# smartGarden_Sen_Rev01.net
KiCad netlist of a schematic drawn in Altium Designer
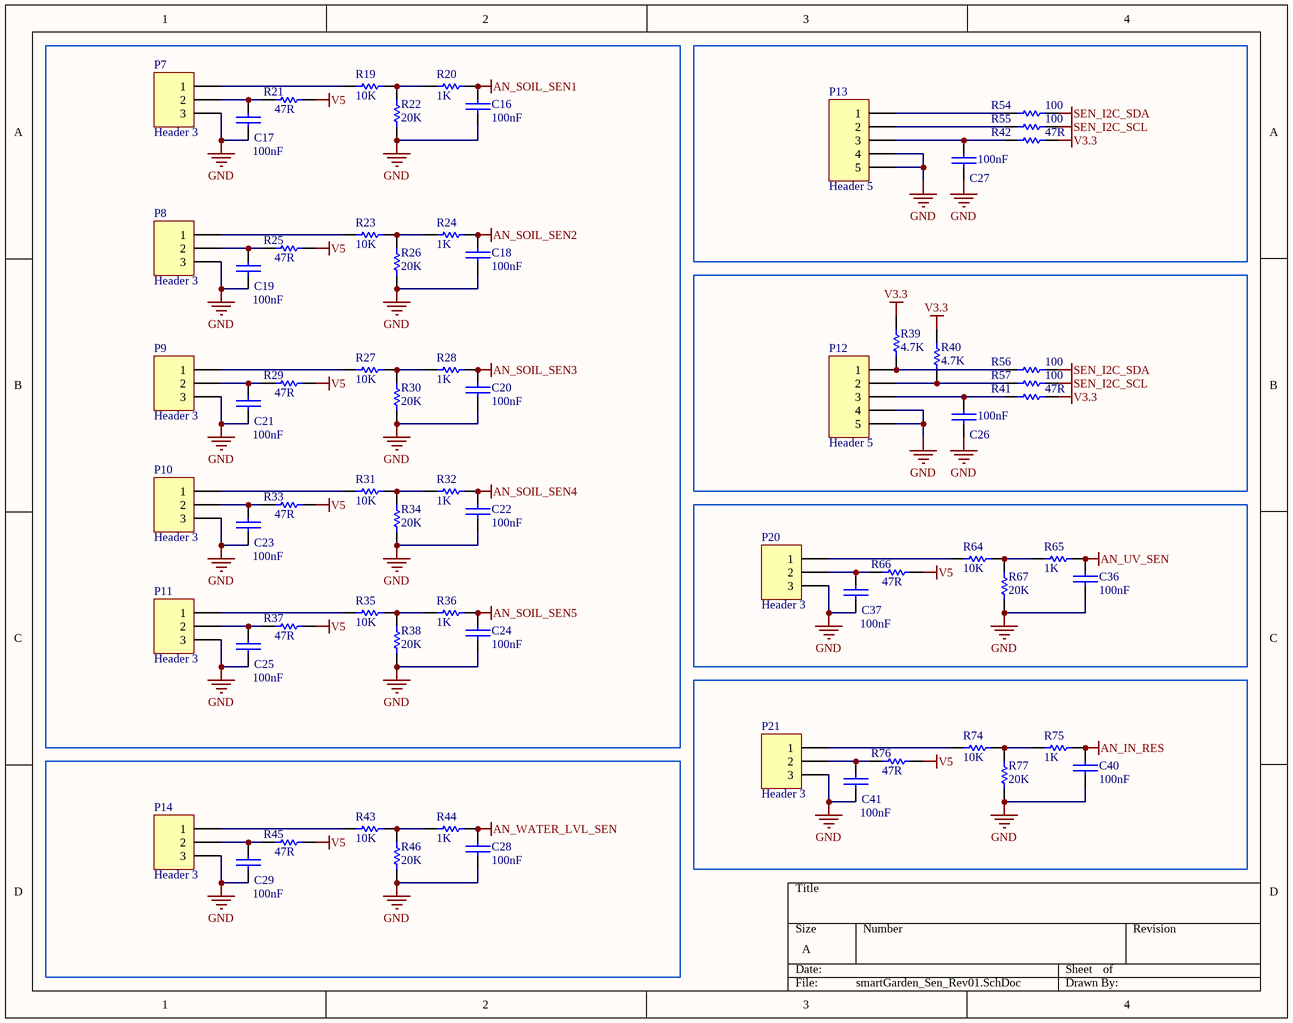
[diagram p0: smartGarden_Sen_Rev01.SchDoc]

(export (version "E")
  (design (tool "Eeschema 10.0.6"))
  (components
    (comp (ref "C16")
      (value "100nF")
      (footprint "0805_smd")
      (description "Capacitor")
      (libsource (lib "*") (part "CAP"))
    )
    (comp (ref "C17")
      (value "100nF")
      (footprint "0805_smd")
      (description "Capacitor")
      (libsource (lib "*") (part "CAP"))
    )
    (comp (ref "C18")
      (value "100nF")
      (footprint "0805_smd")
      (description "Capacitor")
      (libsource (lib "*") (part "CAP"))
    )
    (comp (ref "C19")
      (value "100nF")
      (footprint "0805_smd")
      (description "Capacitor")
      (libsource (lib "*") (part "CAP"))
    )
    (comp (ref "C20")
      (value "100nF")
      (footprint "0805_smd")
      (description "Capacitor")
      (libsource (lib "*") (part "CAP"))
    )
    (comp (ref "C21")
      (value "100nF")
      (footprint "0805_smd")
      (description "Capacitor")
      (libsource (lib "*") (part "CAP"))
    )
    (comp (ref "C22")
      (value "100nF")
      (footprint "0805_smd")
      (description "Capacitor")
      (libsource (lib "*") (part "CAP"))
    )
    (comp (ref "C23")
      (value "100nF")
      (footprint "0805_smd")
      (description "Capacitor")
      (libsource (lib "*") (part "CAP"))
    )
    (comp (ref "C24")
      (value "100nF")
      (footprint "0805_smd")
      (description "Capacitor")
      (libsource (lib "*") (part "CAP"))
    )
    (comp (ref "C25")
      (value "100nF")
      (footprint "0805_smd")
      (description "Capacitor")
      (libsource (lib "*") (part "CAP"))
    )
    (comp (ref "C26")
      (value "100nF")
      (footprint "0805_smd")
      (description "Capacitor")
      (libsource (lib "*") (part "CAP"))
    )
    (comp (ref "C27")
      (value "100nF")
      (footprint "0805_smd")
      (description "Capacitor")
      (libsource (lib "*") (part "CAP"))
    )
    (comp (ref "C28")
      (value "100nF")
      (footprint "0805_smd")
      (description "Capacitor")
      (libsource (lib "*") (part "CAP"))
    )
    (comp (ref "C29")
      (value "100nF")
      (footprint "0805_smd")
      (description "Capacitor")
      (libsource (lib "*") (part "CAP"))
    )
    (comp (ref "C36")
      (value "100nF")
      (footprint "0805_smd")
      (description "Capacitor")
      (libsource (lib "*") (part "CAP"))
    )
    (comp (ref "C37")
      (value "100nF")
      (footprint "0805_smd")
      (description "Capacitor")
      (libsource (lib "*") (part "CAP"))
    )
    (comp (ref "C40")
      (value "100nF")
      (footprint "0805_smd")
      (description "Capacitor")
      (libsource (lib "*") (part "CAP"))
    )
    (comp (ref "C41")
      (value "100nF")
      (footprint "0805_smd")
      (description "Capacitor")
      (libsource (lib "*") (part "CAP"))
    )
    (comp (ref "P7")
      (value "Header 3")
      (footprint "HDR1X3")
      (description "Header, 3-Pin")
      (fields (field (name "PUBLISHER") "Altium Limited"))
      (libsource (lib "Miscellaneous Connectors") (part "Header 3"))
    )
    (comp (ref "P8")
      (value "Header 3")
      (footprint "HDR1X3")
      (description "Header, 3-Pin")
      (fields (field (name "PUBLISHER") "Altium Limited"))
      (libsource (lib "Miscellaneous Connectors") (part "Header 3"))
    )
    (comp (ref "P9")
      (value "Header 3")
      (footprint "HDR1X3")
      (description "Header, 3-Pin")
      (fields (field (name "PUBLISHER") "Altium Limited"))
      (libsource (lib "Miscellaneous Connectors") (part "Header 3"))
    )
    (comp (ref "P10")
      (value "Header 3")
      (footprint "HDR1X3")
      (description "Header, 3-Pin")
      (fields (field (name "PUBLISHER") "Altium Limited"))
      (libsource (lib "Miscellaneous Connectors") (part "Header 3"))
    )
    (comp (ref "P11")
      (value "Header 3")
      (footprint "HDR1X3")
      (description "Header, 3-Pin")
      (fields (field (name "PUBLISHER") "Altium Limited"))
      (libsource (lib "Miscellaneous Connectors") (part "Header 3"))
    )
    (comp (ref "P12")
      (value "Header 5")
      (footprint "HDR1X5")
      (description "Header, 5-Pin")
      (fields (field (name "PUBLISHER") "Altium Limited"))
      (libsource (lib "Miscellaneous Connectors") (part "Header 5"))
    )
    (comp (ref "P13")
      (value "Header 5")
      (footprint "HDR1X5")
      (description "Header, 5-Pin")
      (fields (field (name "PUBLISHER") "Altium Limited"))
      (libsource (lib "Miscellaneous Connectors") (part "Header 5"))
    )
    (comp (ref "P14")
      (value "Header 3")
      (footprint "HDR1X3")
      (description "Header, 3-Pin")
      (fields (field (name "PUBLISHER") "Altium Limited"))
      (libsource (lib "Miscellaneous Connectors") (part "Header 3"))
    )
    (comp (ref "P20")
      (value "Header 3")
      (footprint "HDR1X3")
      (description "Header, 3-Pin")
      (fields (field (name "PUBLISHER") "Altium Limited"))
      (libsource (lib "Miscellaneous Connectors") (part "Header 3"))
    )
    (comp (ref "P21")
      (value "Header 3")
      (footprint "HDR1X3")
      (description "Header, 3-Pin")
      (fields (field (name "PUBLISHER") "Altium Limited"))
      (libsource (lib "Miscellaneous Connectors") (part "Header 3"))
    )
    (comp (ref "R19")
      (value "10K")
      (footprint "0805_smd")
      (description "Resistor")
      (fields (field (name "PUBLISHER") "Altium Limited"))
      (libsource (lib "Miscellaneous Devices") (part "Res1"))
    )
    (comp (ref "R20")
      (value "1K")
      (footprint "0805_smd")
      (description "Resistor")
      (fields (field (name "PUBLISHER") "Altium Limited"))
      (libsource (lib "Miscellaneous Devices") (part "Res1"))
    )
    (comp (ref "R21")
      (value "47R")
      (footprint "0805_smd")
      (description "Resistor")
      (fields (field (name "PUBLISHER") "Altium Limited"))
      (libsource (lib "Miscellaneous Devices") (part "Res1"))
    )
    (comp (ref "R22")
      (value "20K")
      (footprint "0805_smd")
      (description "Resistor")
      (fields (field (name "PUBLISHER") "Altium Limited"))
      (libsource (lib "Miscellaneous Devices") (part "Res1"))
    )
    (comp (ref "R23")
      (value "10K")
      (footprint "0805_smd")
      (description "Resistor")
      (fields (field (name "PUBLISHER") "Altium Limited"))
      (libsource (lib "Miscellaneous Devices") (part "Res1"))
    )
    (comp (ref "R24")
      (value "1K")
      (footprint "0805_smd")
      (description "Resistor")
      (fields (field (name "PUBLISHER") "Altium Limited"))
      (libsource (lib "Miscellaneous Devices") (part "Res1"))
    )
    (comp (ref "R25")
      (value "47R")
      (footprint "0805_smd")
      (description "Resistor")
      (fields (field (name "PUBLISHER") "Altium Limited"))
      (libsource (lib "Miscellaneous Devices") (part "Res1"))
    )
    (comp (ref "R26")
      (value "20K")
      (footprint "0805_smd")
      (description "Resistor")
      (fields (field (name "PUBLISHER") "Altium Limited"))
      (libsource (lib "Miscellaneous Devices") (part "Res1"))
    )
    (comp (ref "R27")
      (value "10K")
      (footprint "0805_smd")
      (description "Resistor")
      (fields (field (name "PUBLISHER") "Altium Limited"))
      (libsource (lib "Miscellaneous Devices") (part "Res1"))
    )
    (comp (ref "R28")
      (value "1K")
      (footprint "0805_smd")
      (description "Resistor")
      (fields (field (name "PUBLISHER") "Altium Limited"))
      (libsource (lib "Miscellaneous Devices") (part "Res1"))
    )
    (comp (ref "R29")
      (value "47R")
      (footprint "0805_smd")
      (description "Resistor")
      (fields (field (name "PUBLISHER") "Altium Limited"))
      (libsource (lib "Miscellaneous Devices") (part "Res1"))
    )
    (comp (ref "R30")
      (value "20K")
      (footprint "0805_smd")
      (description "Resistor")
      (fields (field (name "PUBLISHER") "Altium Limited"))
      (libsource (lib "Miscellaneous Devices") (part "Res1"))
    )
    (comp (ref "R31")
      (value "10K")
      (footprint "0805_smd")
      (description "Resistor")
      (fields (field (name "PUBLISHER") "Altium Limited"))
      (libsource (lib "Miscellaneous Devices") (part "Res1"))
    )
    (comp (ref "R32")
      (value "1K")
      (footprint "0805_smd")
      (description "Resistor")
      (fields (field (name "PUBLISHER") "Altium Limited"))
      (libsource (lib "Miscellaneous Devices") (part "Res1"))
    )
    (comp (ref "R33")
      (value "47R")
      (footprint "0805_smd")
      (description "Resistor")
      (fields (field (name "PUBLISHER") "Altium Limited"))
      (libsource (lib "Miscellaneous Devices") (part "Res1"))
    )
    (comp (ref "R34")
      (value "20K")
      (footprint "0805_smd")
      (description "Resistor")
      (fields (field (name "PUBLISHER") "Altium Limited"))
      (libsource (lib "Miscellaneous Devices") (part "Res1"))
    )
    (comp (ref "R35")
      (value "10K")
      (footprint "0805_smd")
      (description "Resistor")
      (fields (field (name "PUBLISHER") "Altium Limited"))
      (libsource (lib "Miscellaneous Devices") (part "Res1"))
    )
    (comp (ref "R36")
      (value "1K")
      (footprint "0805_smd")
      (description "Resistor")
      (fields (field (name "PUBLISHER") "Altium Limited"))
      (libsource (lib "Miscellaneous Devices") (part "Res1"))
    )
    (comp (ref "R37")
      (value "47R")
      (footprint "0805_smd")
      (description "Resistor")
      (fields (field (name "PUBLISHER") "Altium Limited"))
      (libsource (lib "Miscellaneous Devices") (part "Res1"))
    )
    (comp (ref "R38")
      (value "20K")
      (footprint "0805_smd")
      (description "Resistor")
      (fields (field (name "PUBLISHER") "Altium Limited"))
      (libsource (lib "Miscellaneous Devices") (part "Res1"))
    )
    (comp (ref "R39")
      (value "4.7K")
      (footprint "0805_smd")
      (description "Resistor")
      (fields (field (name "PUBLISHER") "Altium Limited"))
      (libsource (lib "Miscellaneous Devices") (part "Res1"))
    )
    (comp (ref "R40")
      (value "4.7K")
      (footprint "0805_smd")
      (description "Resistor")
      (fields (field (name "PUBLISHER") "Altium Limited"))
      (libsource (lib "Miscellaneous Devices") (part "Res1"))
    )
    (comp (ref "R41")
      (value "47R")
      (footprint "0805_smd")
      (description "Resistor")
      (fields (field (name "PUBLISHER") "Altium Limited"))
      (libsource (lib "Miscellaneous Devices") (part "Res1"))
    )
    (comp (ref "R42")
      (value "47R")
      (footprint "0805_smd")
      (description "Resistor")
      (fields (field (name "PUBLISHER") "Altium Limited"))
      (libsource (lib "Miscellaneous Devices") (part "Res1"))
    )
    (comp (ref "R43")
      (value "10K")
      (footprint "0805_smd")
      (description "Resistor")
      (fields (field (name "PUBLISHER") "Altium Limited"))
      (libsource (lib "Miscellaneous Devices") (part "Res1"))
    )
    (comp (ref "R44")
      (value "1K")
      (footprint "0805_smd")
      (description "Resistor")
      (fields (field (name "PUBLISHER") "Altium Limited"))
      (libsource (lib "Miscellaneous Devices") (part "Res1"))
    )
    (comp (ref "R45")
      (value "47R")
      (footprint "0805_smd")
      (description "Resistor")
      (fields (field (name "PUBLISHER") "Altium Limited"))
      (libsource (lib "Miscellaneous Devices") (part "Res1"))
    )
    (comp (ref "R46")
      (value "20K")
      (footprint "0805_smd")
      (description "Resistor")
      (fields (field (name "PUBLISHER") "Altium Limited"))
      (libsource (lib "Miscellaneous Devices") (part "Res1"))
    )
    (comp (ref "R54")
      (value "100")
      (footprint "0805_smd")
      (description "Resistor")
      (fields (field (name "PUBLISHER") "Altium Limited"))
      (libsource (lib "Miscellaneous Devices") (part "Res1"))
    )
    (comp (ref "R55")
      (value "100")
      (footprint "0805_smd")
      (description "Resistor")
      (fields (field (name "PUBLISHER") "Altium Limited"))
      (libsource (lib "Miscellaneous Devices") (part "Res1"))
    )
    (comp (ref "R56")
      (value "100")
      (footprint "0805_smd")
      (description "Resistor")
      (fields (field (name "PUBLISHER") "Altium Limited"))
      (libsource (lib "Miscellaneous Devices") (part "Res1"))
    )
    (comp (ref "R57")
      (value "100")
      (footprint "0805_smd")
      (description "Resistor")
      (fields (field (name "PUBLISHER") "Altium Limited"))
      (libsource (lib "Miscellaneous Devices") (part "Res1"))
    )
    (comp (ref "R64")
      (value "10K")
      (footprint "0805_smd")
      (description "Resistor")
      (fields (field (name "PUBLISHER") "Altium Limited"))
      (libsource (lib "Miscellaneous Devices") (part "Res1"))
    )
    (comp (ref "R65")
      (value "1K")
      (footprint "0805_smd")
      (description "Resistor")
      (fields (field (name "PUBLISHER") "Altium Limited"))
      (libsource (lib "Miscellaneous Devices") (part "Res1"))
    )
    (comp (ref "R66")
      (value "47R")
      (footprint "0805_smd")
      (description "Resistor")
      (fields (field (name "PUBLISHER") "Altium Limited"))
      (libsource (lib "Miscellaneous Devices") (part "Res1"))
    )
    (comp (ref "R67")
      (value "20K")
      (footprint "0805_smd")
      (description "Resistor")
      (fields (field (name "PUBLISHER") "Altium Limited"))
      (libsource (lib "Miscellaneous Devices") (part "Res1"))
    )
    (comp (ref "R74")
      (value "10K")
      (footprint "0805_smd")
      (description "Resistor")
      (fields (field (name "PUBLISHER") "Altium Limited"))
      (libsource (lib "Miscellaneous Devices") (part "Res1"))
    )
    (comp (ref "R75")
      (value "1K")
      (footprint "0805_smd")
      (description "Resistor")
      (fields (field (name "PUBLISHER") "Altium Limited"))
      (libsource (lib "Miscellaneous Devices") (part "Res1"))
    )
    (comp (ref "R76")
      (value "47R")
      (footprint "0805_smd")
      (description "Resistor")
      (fields (field (name "PUBLISHER") "Altium Limited"))
      (libsource (lib "Miscellaneous Devices") (part "Res1"))
    )
    (comp (ref "R77")
      (value "20K")
      (footprint "0805_smd")
      (description "Resistor")
      (fields (field (name "PUBLISHER") "Altium Limited"))
      (libsource (lib "Miscellaneous Devices") (part "Res1"))
    )
  )
  (nets
    (net (code "1") (name "AN_IN_RES") (class "Default")
      (node (ref "C40") (pin "2") (pinfunction "2_2") (pintype "passive"))
      (node (ref "R75") (pin "1") (pinfunction "1_1") (pintype "passive"))
    )
    (net (code "2") (name "AN_SOIL_SEN1") (class "Default")
      (node (ref "C16") (pin "2") (pinfunction "2_2") (pintype "passive"))
      (node (ref "R20") (pin "1") (pinfunction "1_1") (pintype "passive"))
    )
    (net (code "3") (name "AN_SOIL_SEN2") (class "Default")
      (node (ref "C18") (pin "2") (pinfunction "2_2") (pintype "passive"))
      (node (ref "R24") (pin "1") (pinfunction "1_1") (pintype "passive"))
    )
    (net (code "4") (name "AN_SOIL_SEN3") (class "Default")
      (node (ref "C20") (pin "2") (pinfunction "2_2") (pintype "passive"))
      (node (ref "R28") (pin "1") (pinfunction "1_1") (pintype "passive"))
    )
    (net (code "5") (name "AN_SOIL_SEN4") (class "Default")
      (node (ref "C22") (pin "2") (pinfunction "2_2") (pintype "passive"))
      (node (ref "R32") (pin "1") (pinfunction "1_1") (pintype "passive"))
    )
    (net (code "6") (name "AN_SOIL_SEN5") (class "Default")
      (node (ref "C24") (pin "2") (pinfunction "2_2") (pintype "passive"))
      (node (ref "R36") (pin "1") (pinfunction "1_1") (pintype "passive"))
    )
    (net (code "7") (name "AN_UV_SEN") (class "Default")
      (node (ref "C36") (pin "2") (pinfunction "2_2") (pintype "passive"))
      (node (ref "R65") (pin "1") (pinfunction "1_1") (pintype "passive"))
    )
    (net (code "8") (name "AN_WATER_LVL_SEN") (class "Default")
      (node (ref "C28") (pin "2") (pinfunction "2_2") (pintype "passive"))
      (node (ref "R44") (pin "1") (pinfunction "1_1") (pintype "passive"))
    )
    (net (code "9") (name "GND") (class "Default")
      (node (ref "C16") (pin "1") (pinfunction "1_1") (pintype "passive"))
      (node (ref "C17") (pin "1") (pinfunction "1_1") (pintype "passive"))
      (node (ref "C18") (pin "1") (pinfunction "1_1") (pintype "passive"))
      (node (ref "C19") (pin "1") (pinfunction "1_1") (pintype "passive"))
      (node (ref "C20") (pin "1") (pinfunction "1_1") (pintype "passive"))
      (node (ref "C21") (pin "1") (pinfunction "1_1") (pintype "passive"))
      (node (ref "C22") (pin "1") (pinfunction "1_1") (pintype "passive"))
      (node (ref "C23") (pin "1") (pinfunction "1_1") (pintype "passive"))
      (node (ref "C24") (pin "1") (pinfunction "1_1") (pintype "passive"))
      (node (ref "C25") (pin "1") (pinfunction "1_1") (pintype "passive"))
      (node (ref "C26") (pin "1") (pinfunction "1_1") (pintype "passive"))
      (node (ref "C27") (pin "1") (pinfunction "1_1") (pintype "passive"))
      (node (ref "C28") (pin "1") (pinfunction "1_1") (pintype "passive"))
      (node (ref "C29") (pin "1") (pinfunction "1_1") (pintype "passive"))
      (node (ref "C36") (pin "1") (pinfunction "1_1") (pintype "passive"))
      (node (ref "C37") (pin "1") (pinfunction "1_1") (pintype "passive"))
      (node (ref "C40") (pin "1") (pinfunction "1_1") (pintype "passive"))
      (node (ref "C41") (pin "1") (pinfunction "1_1") (pintype "passive"))
      (node (ref "P10") (pin "3") (pinfunction "3_3") (pintype "passive"))
      (node (ref "P11") (pin "3") (pinfunction "3_3") (pintype "passive"))
      (node (ref "P12") (pin "4") (pinfunction "4_4") (pintype "passive"))
      (node (ref "P12") (pin "5") (pinfunction "5_5") (pintype "passive"))
      (node (ref "P13") (pin "4") (pinfunction "4_4") (pintype "passive"))
      (node (ref "P13") (pin "5") (pinfunction "5_5") (pintype "passive"))
      (node (ref "P14") (pin "3") (pinfunction "3_3") (pintype "passive"))
      (node (ref "P20") (pin "3") (pinfunction "3_3") (pintype "passive"))
      (node (ref "P21") (pin "3") (pinfunction "3_3") (pintype "passive"))
      (node (ref "P7") (pin "3") (pinfunction "3_3") (pintype "passive"))
      (node (ref "P8") (pin "3") (pinfunction "3_3") (pintype "passive"))
      (node (ref "P9") (pin "3") (pinfunction "3_3") (pintype "passive"))
      (node (ref "R22") (pin "2") (pinfunction "2_2") (pintype "passive"))
      (node (ref "R26") (pin "2") (pinfunction "2_2") (pintype "passive"))
      (node (ref "R30") (pin "2") (pinfunction "2_2") (pintype "passive"))
      (node (ref "R34") (pin "2") (pinfunction "2_2") (pintype "passive"))
      (node (ref "R38") (pin "2") (pinfunction "2_2") (pintype "passive"))
      (node (ref "R46") (pin "2") (pinfunction "2_2") (pintype "passive"))
      (node (ref "R67") (pin "2") (pinfunction "2_2") (pintype "passive"))
      (node (ref "R77") (pin "2") (pinfunction "2_2") (pintype "passive"))
    )
    (net (code "10") (name "Net-(C17-Pad2)") (class "Default")
      (node (ref "C17") (pin "2") (pinfunction "2_2") (pintype "passive"))
      (node (ref "P7") (pin "2") (pinfunction "2_2") (pintype "passive"))
      (node (ref "R21") (pin "2") (pinfunction "2_2") (pintype "passive"))
    )
    (net (code "11") (name "Net-(C19-Pad2)") (class "Default")
      (node (ref "C19") (pin "2") (pinfunction "2_2") (pintype "passive"))
      (node (ref "P8") (pin "2") (pinfunction "2_2") (pintype "passive"))
      (node (ref "R25") (pin "2") (pinfunction "2_2") (pintype "passive"))
    )
    (net (code "12") (name "Net-(C21-Pad2)") (class "Default")
      (node (ref "C21") (pin "2") (pinfunction "2_2") (pintype "passive"))
      (node (ref "P9") (pin "2") (pinfunction "2_2") (pintype "passive"))
      (node (ref "R29") (pin "2") (pinfunction "2_2") (pintype "passive"))
    )
    (net (code "13") (name "Net-(C23-Pad2)") (class "Default")
      (node (ref "C23") (pin "2") (pinfunction "2_2") (pintype "passive"))
      (node (ref "P10") (pin "2") (pinfunction "2_2") (pintype "passive"))
      (node (ref "R33") (pin "2") (pinfunction "2_2") (pintype "passive"))
    )
    (net (code "14") (name "Net-(C25-Pad2)") (class "Default")
      (node (ref "C25") (pin "2") (pinfunction "2_2") (pintype "passive"))
      (node (ref "P11") (pin "2") (pinfunction "2_2") (pintype "passive"))
      (node (ref "R37") (pin "2") (pinfunction "2_2") (pintype "passive"))
    )
    (net (code "15") (name "Net-(C26-Pad2)") (class "Default")
      (node (ref "C26") (pin "2") (pinfunction "2_2") (pintype "passive"))
      (node (ref "P12") (pin "3") (pinfunction "3_3") (pintype "passive"))
      (node (ref "R41") (pin "2") (pinfunction "2_2") (pintype "passive"))
    )
    (net (code "16") (name "Net-(C27-Pad2)") (class "Default")
      (node (ref "C27") (pin "2") (pinfunction "2_2") (pintype "passive"))
      (node (ref "P13") (pin "3") (pinfunction "3_3") (pintype "passive"))
      (node (ref "R42") (pin "2") (pinfunction "2_2") (pintype "passive"))
    )
    (net (code "17") (name "Net-(C29-Pad2)") (class "Default")
      (node (ref "C29") (pin "2") (pinfunction "2_2") (pintype "passive"))
      (node (ref "P14") (pin "2") (pinfunction "2_2") (pintype "passive"))
      (node (ref "R45") (pin "2") (pinfunction "2_2") (pintype "passive"))
    )
    (net (code "18") (name "Net-(C37-Pad2)") (class "Default")
      (node (ref "C37") (pin "2") (pinfunction "2_2") (pintype "passive"))
      (node (ref "P20") (pin "2") (pinfunction "2_2") (pintype "passive"))
      (node (ref "R66") (pin "2") (pinfunction "2_2") (pintype "passive"))
    )
    (net (code "19") (name "Net-(C41-Pad2)") (class "Default")
      (node (ref "C41") (pin "2") (pinfunction "2_2") (pintype "passive"))
      (node (ref "P21") (pin "2") (pinfunction "2_2") (pintype "passive"))
      (node (ref "R76") (pin "2") (pinfunction "2_2") (pintype "passive"))
    )
    (net (code "20") (name "Net-(P7-Pad1)") (class "Default")
      (node (ref "P7") (pin "1") (pinfunction "1_1") (pintype "passive"))
      (node (ref "R19") (pin "2") (pinfunction "2_2") (pintype "passive"))
    )
    (net (code "21") (name "Net-(P8-Pad1)") (class "Default")
      (node (ref "P8") (pin "1") (pinfunction "1_1") (pintype "passive"))
      (node (ref "R23") (pin "2") (pinfunction "2_2") (pintype "passive"))
    )
    (net (code "22") (name "Net-(P9-Pad1)") (class "Default")
      (node (ref "P9") (pin "1") (pinfunction "1_1") (pintype "passive"))
      (node (ref "R27") (pin "2") (pinfunction "2_2") (pintype "passive"))
    )
    (net (code "23") (name "Net-(P10-Pad1)") (class "Default")
      (node (ref "P10") (pin "1") (pinfunction "1_1") (pintype "passive"))
      (node (ref "R31") (pin "2") (pinfunction "2_2") (pintype "passive"))
    )
    (net (code "24") (name "Net-(P11-Pad1)") (class "Default")
      (node (ref "P11") (pin "1") (pinfunction "1_1") (pintype "passive"))
      (node (ref "R35") (pin "2") (pinfunction "2_2") (pintype "passive"))
    )
    (net (code "25") (name "Net-(P12-Pad1)") (class "Default")
      (node (ref "P12") (pin "1") (pinfunction "1_1") (pintype "passive"))
      (node (ref "R39") (pin "2") (pinfunction "2_2") (pintype "passive"))
      (node (ref "R56") (pin "2") (pinfunction "2_2") (pintype "passive"))
    )
    (net (code "26") (name "Net-(P12-Pad2)") (class "Default")
      (node (ref "P12") (pin "2") (pinfunction "2_2") (pintype "passive"))
      (node (ref "R40") (pin "2") (pinfunction "2_2") (pintype "passive"))
      (node (ref "R57") (pin "2") (pinfunction "2_2") (pintype "passive"))
    )
    (net (code "27") (name "Net-(P13-Pad1)") (class "Default")
      (node (ref "P13") (pin "1") (pinfunction "1_1") (pintype "passive"))
      (node (ref "R54") (pin "2") (pinfunction "2_2") (pintype "passive"))
    )
    (net (code "28") (name "Net-(P13-Pad2)") (class "Default")
      (node (ref "P13") (pin "2") (pinfunction "2_2") (pintype "passive"))
      (node (ref "R55") (pin "2") (pinfunction "2_2") (pintype "passive"))
    )
    (net (code "29") (name "Net-(P14-Pad1)") (class "Default")
      (node (ref "P14") (pin "1") (pinfunction "1_1") (pintype "passive"))
      (node (ref "R43") (pin "2") (pinfunction "2_2") (pintype "passive"))
    )
    (net (code "30") (name "Net-(P20-Pad1)") (class "Default")
      (node (ref "P20") (pin "1") (pinfunction "1_1") (pintype "passive"))
      (node (ref "R64") (pin "2") (pinfunction "2_2") (pintype "passive"))
    )
    (net (code "31") (name "Net-(P21-Pad1)") (class "Default")
      (node (ref "P21") (pin "1") (pinfunction "1_1") (pintype "passive"))
      (node (ref "R74") (pin "2") (pinfunction "2_2") (pintype "passive"))
    )
    (net (code "32") (name "Net-(R19-Pad1)") (class "Default")
      (node (ref "R19") (pin "1") (pinfunction "1_1") (pintype "passive"))
      (node (ref "R20") (pin "2") (pinfunction "2_2") (pintype "passive"))
      (node (ref "R22") (pin "1") (pinfunction "1_1") (pintype "passive"))
    )
    (net (code "33") (name "Net-(R23-Pad1)") (class "Default")
      (node (ref "R23") (pin "1") (pinfunction "1_1") (pintype "passive"))
      (node (ref "R24") (pin "2") (pinfunction "2_2") (pintype "passive"))
      (node (ref "R26") (pin "1") (pinfunction "1_1") (pintype "passive"))
    )
    (net (code "34") (name "Net-(R27-Pad1)") (class "Default")
      (node (ref "R27") (pin "1") (pinfunction "1_1") (pintype "passive"))
      (node (ref "R28") (pin "2") (pinfunction "2_2") (pintype "passive"))
      (node (ref "R30") (pin "1") (pinfunction "1_1") (pintype "passive"))
    )
    (net (code "35") (name "Net-(R31-Pad1)") (class "Default")
      (node (ref "R31") (pin "1") (pinfunction "1_1") (pintype "passive"))
      (node (ref "R32") (pin "2") (pinfunction "2_2") (pintype "passive"))
      (node (ref "R34") (pin "1") (pinfunction "1_1") (pintype "passive"))
    )
    (net (code "36") (name "Net-(R35-Pad1)") (class "Default")
      (node (ref "R35") (pin "1") (pinfunction "1_1") (pintype "passive"))
      (node (ref "R36") (pin "2") (pinfunction "2_2") (pintype "passive"))
      (node (ref "R38") (pin "1") (pinfunction "1_1") (pintype "passive"))
    )
    (net (code "37") (name "Net-(R43-Pad1)") (class "Default")
      (node (ref "R43") (pin "1") (pinfunction "1_1") (pintype "passive"))
      (node (ref "R44") (pin "2") (pinfunction "2_2") (pintype "passive"))
      (node (ref "R46") (pin "1") (pinfunction "1_1") (pintype "passive"))
    )
    (net (code "38") (name "Net-(R64-Pad1)") (class "Default")
      (node (ref "R64") (pin "1") (pinfunction "1_1") (pintype "passive"))
      (node (ref "R65") (pin "2") (pinfunction "2_2") (pintype "passive"))
      (node (ref "R67") (pin "1") (pinfunction "1_1") (pintype "passive"))
    )
    (net (code "39") (name "Net-(R74-Pad1)") (class "Default")
      (node (ref "R74") (pin "1") (pinfunction "1_1") (pintype "passive"))
      (node (ref "R75") (pin "2") (pinfunction "2_2") (pintype "passive"))
      (node (ref "R77") (pin "1") (pinfunction "1_1") (pintype "passive"))
    )
    (net (code "40") (name "SEN_I2C_SCL") (class "Default")
      (node (ref "R55") (pin "1") (pinfunction "1_1") (pintype "passive"))
      (node (ref "R57") (pin "1") (pinfunction "1_1") (pintype "passive"))
    )
    (net (code "41") (name "SEN_I2C_SDA") (class "Default")
      (node (ref "R54") (pin "1") (pinfunction "1_1") (pintype "passive"))
      (node (ref "R56") (pin "1") (pinfunction "1_1") (pintype "passive"))
    )
    (net (code "42") (name "V3.3") (class "Default")
      (node (ref "R39") (pin "1") (pinfunction "1_1") (pintype "passive"))
      (node (ref "R40") (pin "1") (pinfunction "1_1") (pintype "passive"))
      (node (ref "R41") (pin "1") (pinfunction "1_1") (pintype "passive"))
      (node (ref "R42") (pin "1") (pinfunction "1_1") (pintype "passive"))
    )
    (net (code "43") (name "V5") (class "Default")
      (node (ref "R21") (pin "1") (pinfunction "1_1") (pintype "passive"))
      (node (ref "R25") (pin "1") (pinfunction "1_1") (pintype "passive"))
      (node (ref "R29") (pin "1") (pinfunction "1_1") (pintype "passive"))
      (node (ref "R33") (pin "1") (pinfunction "1_1") (pintype "passive"))
      (node (ref "R37") (pin "1") (pinfunction "1_1") (pintype "passive"))
      (node (ref "R45") (pin "1") (pinfunction "1_1") (pintype "passive"))
      (node (ref "R66") (pin "1") (pinfunction "1_1") (pintype "passive"))
      (node (ref "R76") (pin "1") (pinfunction "1_1") (pintype "passive"))
    )
  )
)
